# LEDDriverSFE002.net
KiCad netlist of a schematic drawn in EAGLE
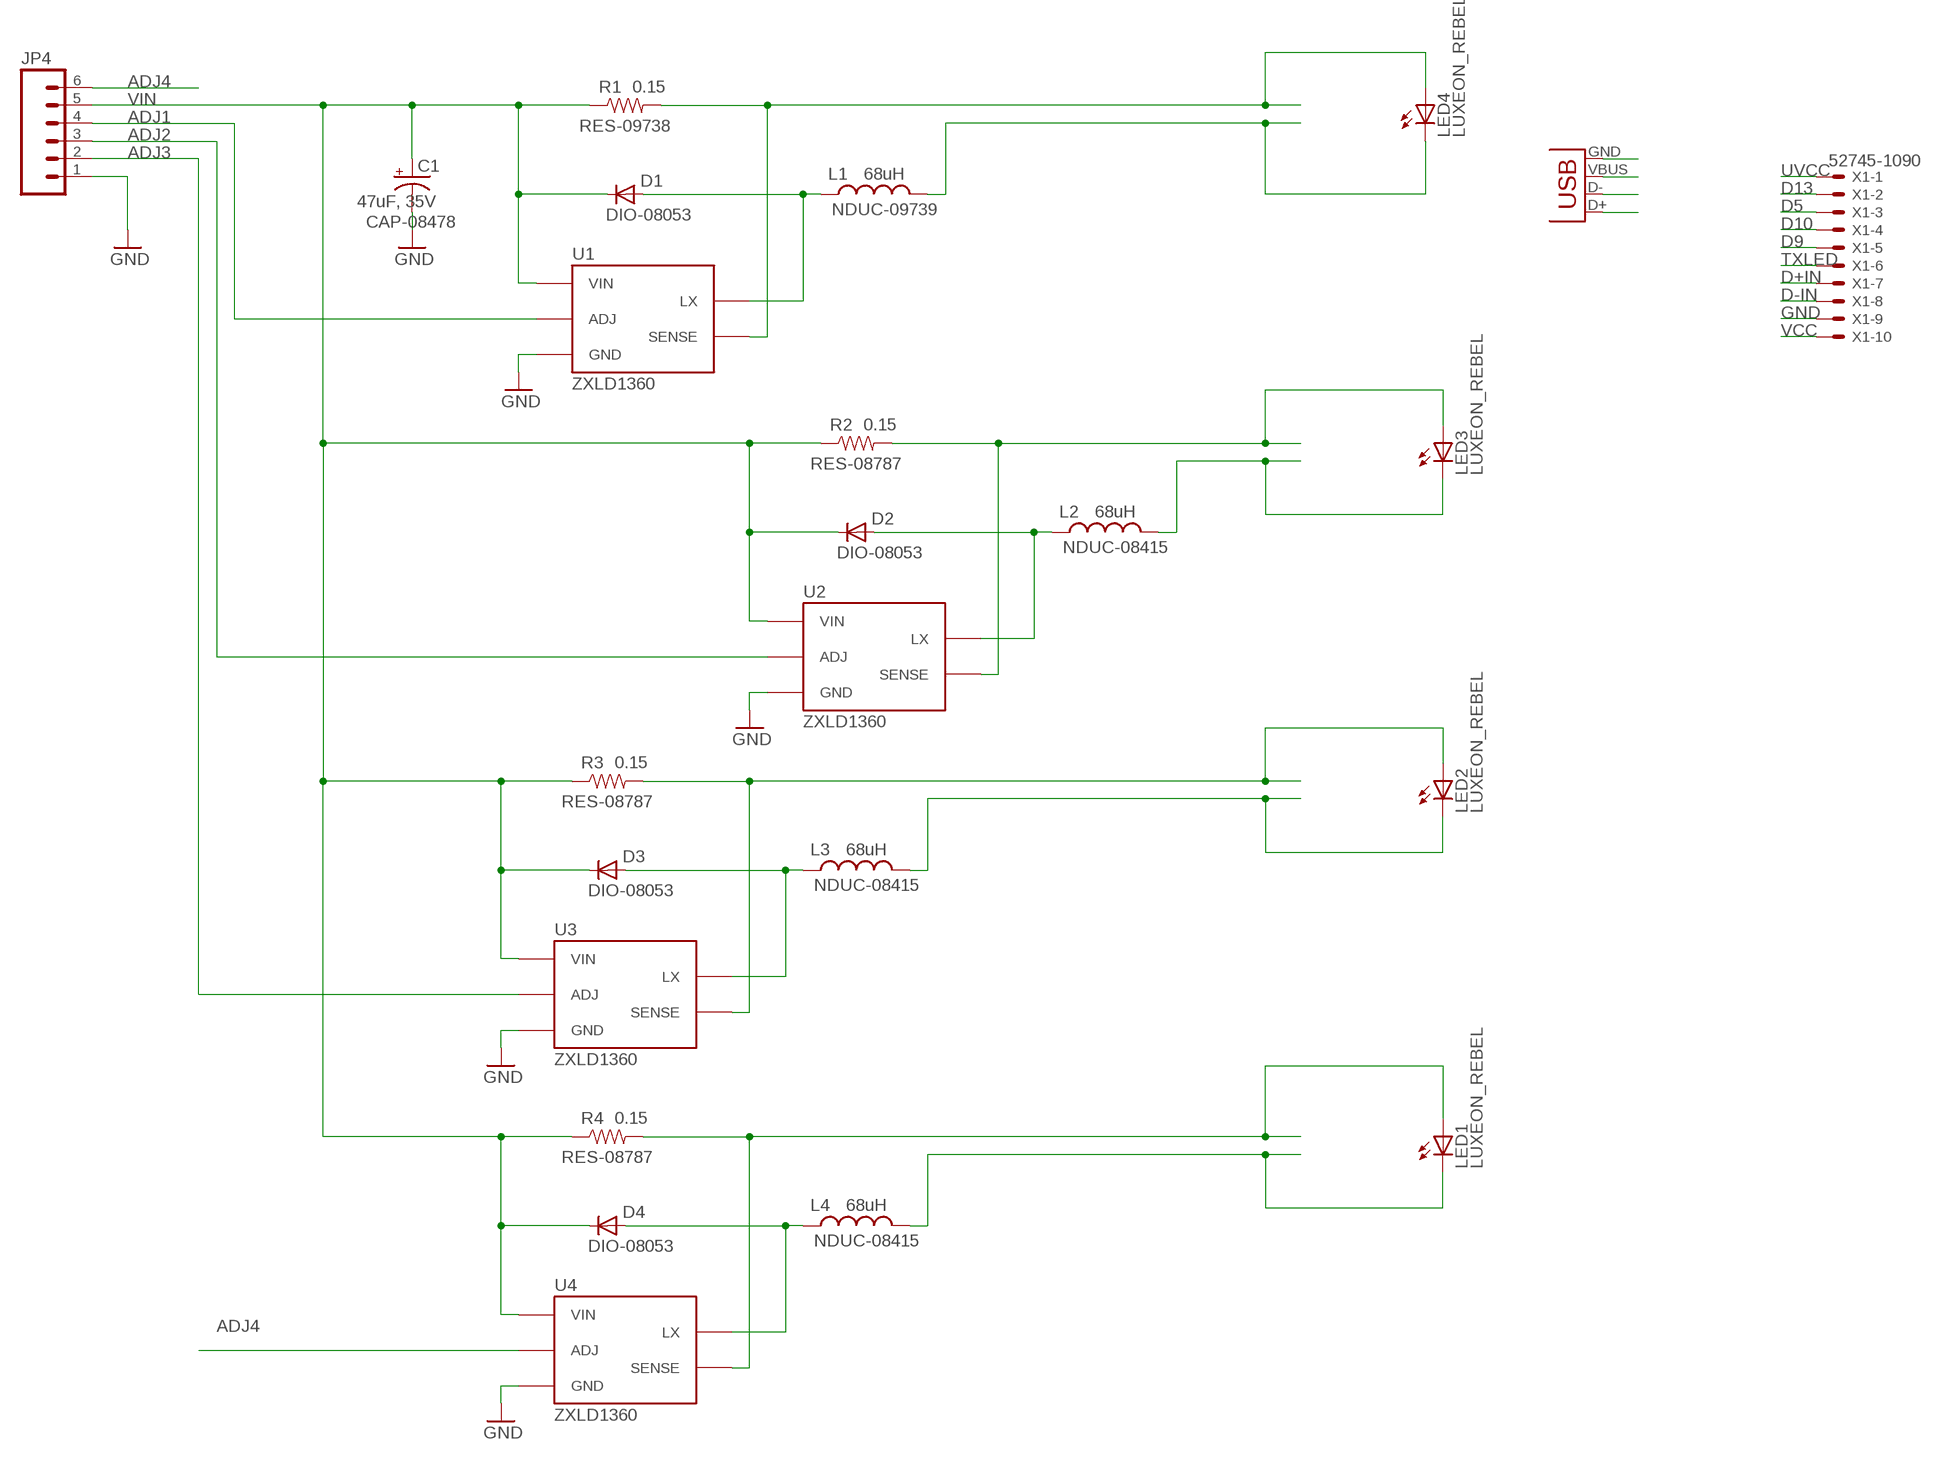
[diagram p0: schematic, sheet 1]

(export (version "E")
  (design (tool "Eeschema 10.0.6"))
  (components
    (comp (ref "C1")
      (value "47uF, 35V")
      (footprint "eagle-import:PANASONIC_D")
      (libsource (lib "eagle-import") (part "CAP_POLD"))
    )
    (comp (ref "D1")
      (value "MBRA140")
      (footprint "eagle-import:SMA-DIODE")
      (libsource (lib "eagle-import") (part "DIODESMA"))
    )
    (comp (ref "D2")
      (value "MBRA140")
      (footprint "eagle-import:SMA-DIODE")
      (libsource (lib "eagle-import") (part "DIODESMA"))
    )
    (comp (ref "D3")
      (value "MBRA140")
      (footprint "eagle-import:SMA-DIODE")
      (libsource (lib "eagle-import") (part "DIODESMA"))
    )
    (comp (ref "D4")
      (value "MBRA140")
      (footprint "eagle-import:SMA-DIODE")
      (libsource (lib "eagle-import") (part "DIODESMA"))
    )
    (comp (ref "JP4")
      (value "M06SIP")
      (footprint "eagle-import:1X06")
      (libsource (lib "eagle-import") (part "M06SIP"))
    )
    (comp (ref "L1")
      (value "68uH")
      (footprint "eagle-import:CR75")
      (libsource (lib "eagle-import") (part "INDUCTORCR75"))
    )
    (comp (ref "L2")
      (value "68uH")
      (footprint "eagle-import:CR75")
      (libsource (lib "eagle-import") (part "INDUCTORCR75"))
    )
    (comp (ref "L3")
      (value "68uH")
      (footprint "eagle-import:CR75")
      (libsource (lib "eagle-import") (part "INDUCTORCR75"))
    )
    (comp (ref "L4")
      (value "68uH")
      (footprint "eagle-import:CR75")
      (libsource (lib "eagle-import") (part "INDUCTORCR75"))
    )
    (comp (ref "LED1")
      (value "LUXEON_REBEL")
      (footprint "eagle-import:LUXEON_REBEL")
      (libsource (lib "eagle-import") (part "LUXEON_REBEL"))
    )
    (comp (ref "LED2")
      (value "LUXEON_REBEL")
      (footprint "eagle-import:LUXEON_REBEL")
      (libsource (lib "eagle-import") (part "LUXEON_REBEL"))
    )
    (comp (ref "LED3")
      (value "LUXEON_REBEL")
      (footprint "eagle-import:LUXEON_REBEL")
      (libsource (lib "eagle-import") (part "LUXEON_REBEL"))
    )
    (comp (ref "LED4")
      (value "LUXEON_REBEL")
      (footprint "eagle-import:LUXEON_REBEL")
      (libsource (lib "eagle-import") (part "LUXEON_REBEL"))
    )
    (comp (ref "R1")
      (value "0.15")
      (footprint "eagle-import:0603-RES")
      (libsource (lib "eagle-import") (part "RESISTOR0603-RES"))
    )
    (comp (ref "R2")
      (value "0.15")
      (footprint "eagle-import:0603-RES")
      (libsource (lib "eagle-import") (part "RESISTOR0603-RES"))
    )
    (comp (ref "R3")
      (value "0.15")
      (footprint "eagle-import:0603-RES")
      (libsource (lib "eagle-import") (part "RESISTOR0603-RES"))
    )
    (comp (ref "R4")
      (value "0.15")
      (footprint "eagle-import:0603-RES")
      (libsource (lib "eagle-import") (part "RESISTOR0603-RES"))
    )
    (comp (ref "U1")
      (value "ZXLD1360")
      (footprint "eagle-import:SOT23-5")
      (libsource (lib "eagle-import") (part "ZXLD1360"))
    )
    (comp (ref "U2")
      (value "ZXLD1360")
      (footprint "eagle-import:SOT23-5")
      (libsource (lib "eagle-import") (part "ZXLD1360"))
    )
    (comp (ref "U3")
      (value "ZXLD1360")
      (footprint "eagle-import:SOT23-5")
      (libsource (lib "eagle-import") (part "ZXLD1360"))
    )
    (comp (ref "U4")
      (value "ZXLD1360")
      (footprint "eagle-import:SOT23-5")
      (libsource (lib "eagle-import") (part "ZXLD1360"))
    )
    (comp (ref "X1")
      (value "52745-1090")
      (footprint "eagle-import:52745-1090")
      (libsource (lib "eagle-import") (part "52745-1090"))
    )
    (comp (ref "X2")
      (value "USB-MICROB")
      (footprint "eagle-import:USB-MICROB")
      (libsource (lib "eagle-import") (part "USB-MICROB"))
    )
  )
  (nets
    (net (code "1") (name "/ADJ1") (class "Default")
      (node (ref "JP4") (pin "4") (pinfunction "4_4") (pintype "passive"))
      (node (ref "U1") (pin "3") (pinfunction "ADJ_3") (pintype "bidirectional"))
    )
    (net (code "2") (name "/ADJ2") (class "Default")
      (node (ref "JP4") (pin "3") (pinfunction "3_3") (pintype "passive"))
      (node (ref "U2") (pin "3") (pinfunction "ADJ_3") (pintype "bidirectional"))
    )
    (net (code "3") (name "/ADJ3") (class "Default")
      (node (ref "JP4") (pin "2") (pinfunction "2_2") (pintype "passive"))
      (node (ref "U3") (pin "3") (pinfunction "ADJ_3") (pintype "bidirectional"))
    )
    (net (code "4") (name "/ADJ4") (class "Default")
      (node (ref "JP4") (pin "6") (pinfunction "6_6") (pintype "passive"))
      (node (ref "U4") (pin "3") (pinfunction "ADJ_3") (pintype "bidirectional"))
    )
    (net (code "5") (name "/D+IN") (class "Default")
      (node (ref "X1") (pin "7") (pinfunction "S_7") (pintype "passive"))
      (node (ref "X2") (pin "D+") (pinfunction "D+_D+") (pintype "bidirectional"))
    )
    (net (code "6") (name "/D-IN") (class "Default")
      (node (ref "X1") (pin "8") (pinfunction "S_8") (pintype "passive"))
      (node (ref "X2") (pin "D-") (pinfunction "D-_D-") (pintype "bidirectional"))
    )
    (net (code "7") (name "/D5") (class "Default")
      (node (ref "X1") (pin "3") (pinfunction "S_3") (pintype "passive"))
    )
    (net (code "8") (name "/D9") (class "Default")
      (node (ref "X1") (pin "5") (pinfunction "S_5") (pintype "passive"))
    )
    (net (code "9") (name "/D10") (class "Default")
      (node (ref "X1") (pin "4") (pinfunction "S_4") (pintype "passive"))
    )
    (net (code "10") (name "/D13") (class "Default")
      (node (ref "X1") (pin "2") (pinfunction "S_2") (pintype "passive"))
    )
    (net (code "11") (name "/TXLED") (class "Default")
      (node (ref "X1") (pin "6") (pinfunction "S_6") (pintype "passive"))
    )
    (net (code "12") (name "/UVCC") (class "Default")
      (node (ref "X1") (pin "1") (pinfunction "S_1") (pintype "passive"))
      (node (ref "X2") (pin "VBUS") (pinfunction "VBUS_VBUS") (pintype "bidirectional"))
    )
    (net (code "13") (name "/VCC") (class "Default")
      (node (ref "X1") (pin "10") (pinfunction "S_10") (pintype "passive"))
    )
    (net (code "14") (name "/VIN") (class "Default")
      (node (ref "C1") (pin "+") (pinfunction "+_+") (pintype "passive"))
      (node (ref "D1") (pin "C") (pinfunction "C_C") (pintype "passive"))
      (node (ref "D2") (pin "C") (pinfunction "C_C") (pintype "passive"))
      (node (ref "D3") (pin "C") (pinfunction "C_C") (pintype "passive"))
      (node (ref "D4") (pin "C") (pinfunction "C_C") (pintype "passive"))
      (node (ref "JP4") (pin "5") (pinfunction "5_5") (pintype "passive"))
      (node (ref "R1") (pin "1") (pinfunction "1_1") (pintype "passive"))
      (node (ref "R2") (pin "1") (pinfunction "1_1") (pintype "passive"))
      (node (ref "R3") (pin "1") (pinfunction "1_1") (pintype "passive"))
      (node (ref "R4") (pin "1") (pinfunction "1_1") (pintype "passive"))
      (node (ref "U1") (pin "5") (pinfunction "VIN_5") (pintype "bidirectional"))
      (node (ref "U2") (pin "5") (pinfunction "VIN_5") (pintype "bidirectional"))
      (node (ref "U3") (pin "5") (pinfunction "VIN_5") (pintype "bidirectional"))
      (node (ref "U4") (pin "5") (pinfunction "VIN_5") (pintype "bidirectional"))
    )
    (net (code "15") (name "GND") (class "Default")
      (node (ref "C1") (pin "-") (pinfunction "-_-") (pintype "passive"))
      (node (ref "JP4") (pin "1") (pinfunction "1_1") (pintype "passive"))
      (node (ref "U1") (pin "2") (pinfunction "GND_2") (pintype "bidirectional"))
      (node (ref "U2") (pin "2") (pinfunction "GND_2") (pintype "bidirectional"))
      (node (ref "U3") (pin "2") (pinfunction "GND_2") (pintype "bidirectional"))
      (node (ref "U4") (pin "2") (pinfunction "GND_2") (pintype "bidirectional"))
      (node (ref "X1") (pin "9") (pinfunction "S_9") (pintype "passive"))
      (node (ref "X2") (pin "GND") (pinfunction "GND_GND") (pintype "bidirectional"))
    )
    (net (code "16") (name "Net-(L1-1)") (class "Default")
      (node (ref "D1") (pin "A") (pinfunction "A_A") (pintype "passive"))
      (node (ref "L1") (pin "P$1") (pinfunction "1_P$1") (pintype "passive"))
      (node (ref "U1") (pin "1") (pinfunction "LX_1") (pintype "bidirectional"))
    )
    (net (code "17") (name "Net-(L1-2)") (class "Default")
      (node (ref "L1") (pin "P$2") (pinfunction "2_P$2") (pintype "passive"))
      (node (ref "LED4") (pin "C") (pinfunction "C_C") (pintype "passive"))
      (node (ref "LED4") (pin "C@1") (pinfunction "C_C@1") (pintype "passive"))
    )
    (net (code "18") (name "Net-(L2-1)") (class "Default")
      (node (ref "D2") (pin "A") (pinfunction "A_A") (pintype "passive"))
      (node (ref "L2") (pin "P$1") (pinfunction "1_P$1") (pintype "passive"))
      (node (ref "U2") (pin "1") (pinfunction "LX_1") (pintype "bidirectional"))
    )
    (net (code "19") (name "Net-(L2-2)") (class "Default")
      (node (ref "L2") (pin "P$2") (pinfunction "2_P$2") (pintype "passive"))
      (node (ref "LED3") (pin "C") (pinfunction "C_C") (pintype "passive"))
      (node (ref "LED3") (pin "C@1") (pinfunction "C_C@1") (pintype "passive"))
    )
    (net (code "20") (name "Net-(L3-1)") (class "Default")
      (node (ref "D3") (pin "A") (pinfunction "A_A") (pintype "passive"))
      (node (ref "L3") (pin "P$1") (pinfunction "1_P$1") (pintype "passive"))
      (node (ref "U3") (pin "1") (pinfunction "LX_1") (pintype "bidirectional"))
    )
    (net (code "21") (name "Net-(L3-2)") (class "Default")
      (node (ref "L3") (pin "P$2") (pinfunction "2_P$2") (pintype "passive"))
      (node (ref "LED2") (pin "C") (pinfunction "C_C") (pintype "passive"))
      (node (ref "LED2") (pin "C@1") (pinfunction "C_C@1") (pintype "passive"))
    )
    (net (code "22") (name "Net-(L4-1)") (class "Default")
      (node (ref "D4") (pin "A") (pinfunction "A_A") (pintype "passive"))
      (node (ref "L4") (pin "P$1") (pinfunction "1_P$1") (pintype "passive"))
      (node (ref "U4") (pin "1") (pinfunction "LX_1") (pintype "bidirectional"))
    )
    (net (code "23") (name "Net-(L4-2)") (class "Default")
      (node (ref "L4") (pin "P$2") (pinfunction "2_P$2") (pintype "passive"))
      (node (ref "LED1") (pin "C") (pinfunction "C_C") (pintype "passive"))
      (node (ref "LED1") (pin "C@1") (pinfunction "C_C@1") (pintype "passive"))
    )
    (net (code "24") (name "Net-(U1-SENSE)") (class "Default")
      (node (ref "LED4") (pin "A") (pinfunction "A_A") (pintype "passive"))
      (node (ref "LED4") (pin "A@1") (pinfunction "A_A@1") (pintype "passive"))
      (node (ref "R1") (pin "2") (pinfunction "2_2") (pintype "passive"))
      (node (ref "U1") (pin "4") (pinfunction "SENSE_4") (pintype "bidirectional"))
    )
    (net (code "25") (name "Net-(U2-SENSE)") (class "Default")
      (node (ref "LED3") (pin "A") (pinfunction "A_A") (pintype "passive"))
      (node (ref "LED3") (pin "A@1") (pinfunction "A_A@1") (pintype "passive"))
      (node (ref "R2") (pin "2") (pinfunction "2_2") (pintype "passive"))
      (node (ref "U2") (pin "4") (pinfunction "SENSE_4") (pintype "bidirectional"))
    )
    (net (code "26") (name "Net-(U3-SENSE)") (class "Default")
      (node (ref "LED2") (pin "A") (pinfunction "A_A") (pintype "passive"))
      (node (ref "LED2") (pin "A@1") (pinfunction "A_A@1") (pintype "passive"))
      (node (ref "R3") (pin "2") (pinfunction "2_2") (pintype "passive"))
      (node (ref "U3") (pin "4") (pinfunction "SENSE_4") (pintype "bidirectional"))
    )
    (net (code "27") (name "Net-(U4-SENSE)") (class "Default")
      (node (ref "LED1") (pin "A") (pinfunction "A_A") (pintype "passive"))
      (node (ref "LED1") (pin "A@1") (pinfunction "A_A@1") (pintype "passive"))
      (node (ref "R4") (pin "2") (pinfunction "2_2") (pintype "passive"))
      (node (ref "U4") (pin "4") (pinfunction "SENSE_4") (pintype "bidirectional"))
    )
  )
)
